# bbshd.net
KiCad netlist of a schematic drawn in EAGLE
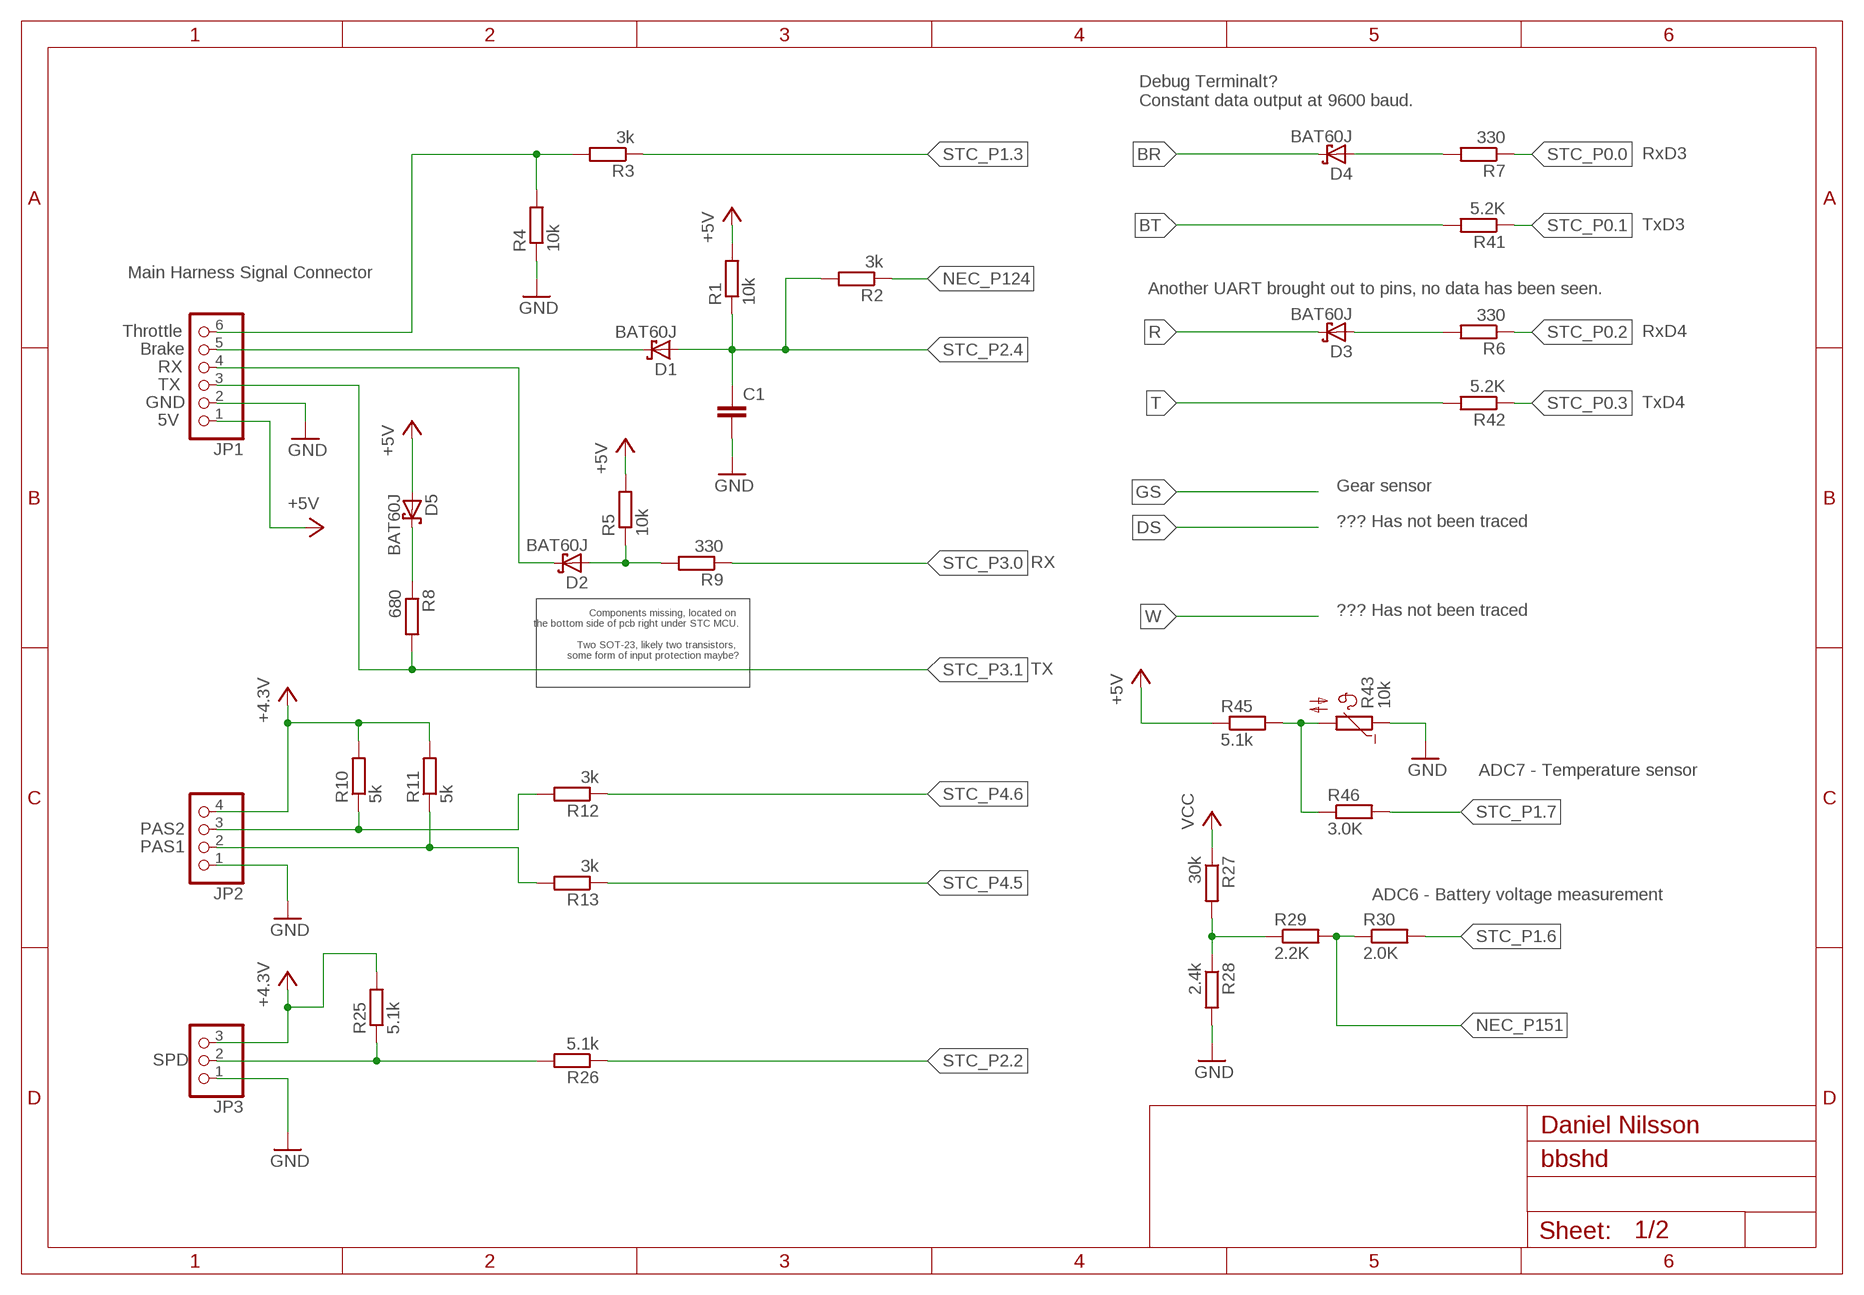
[diagram p0: schematic, sheet 1]
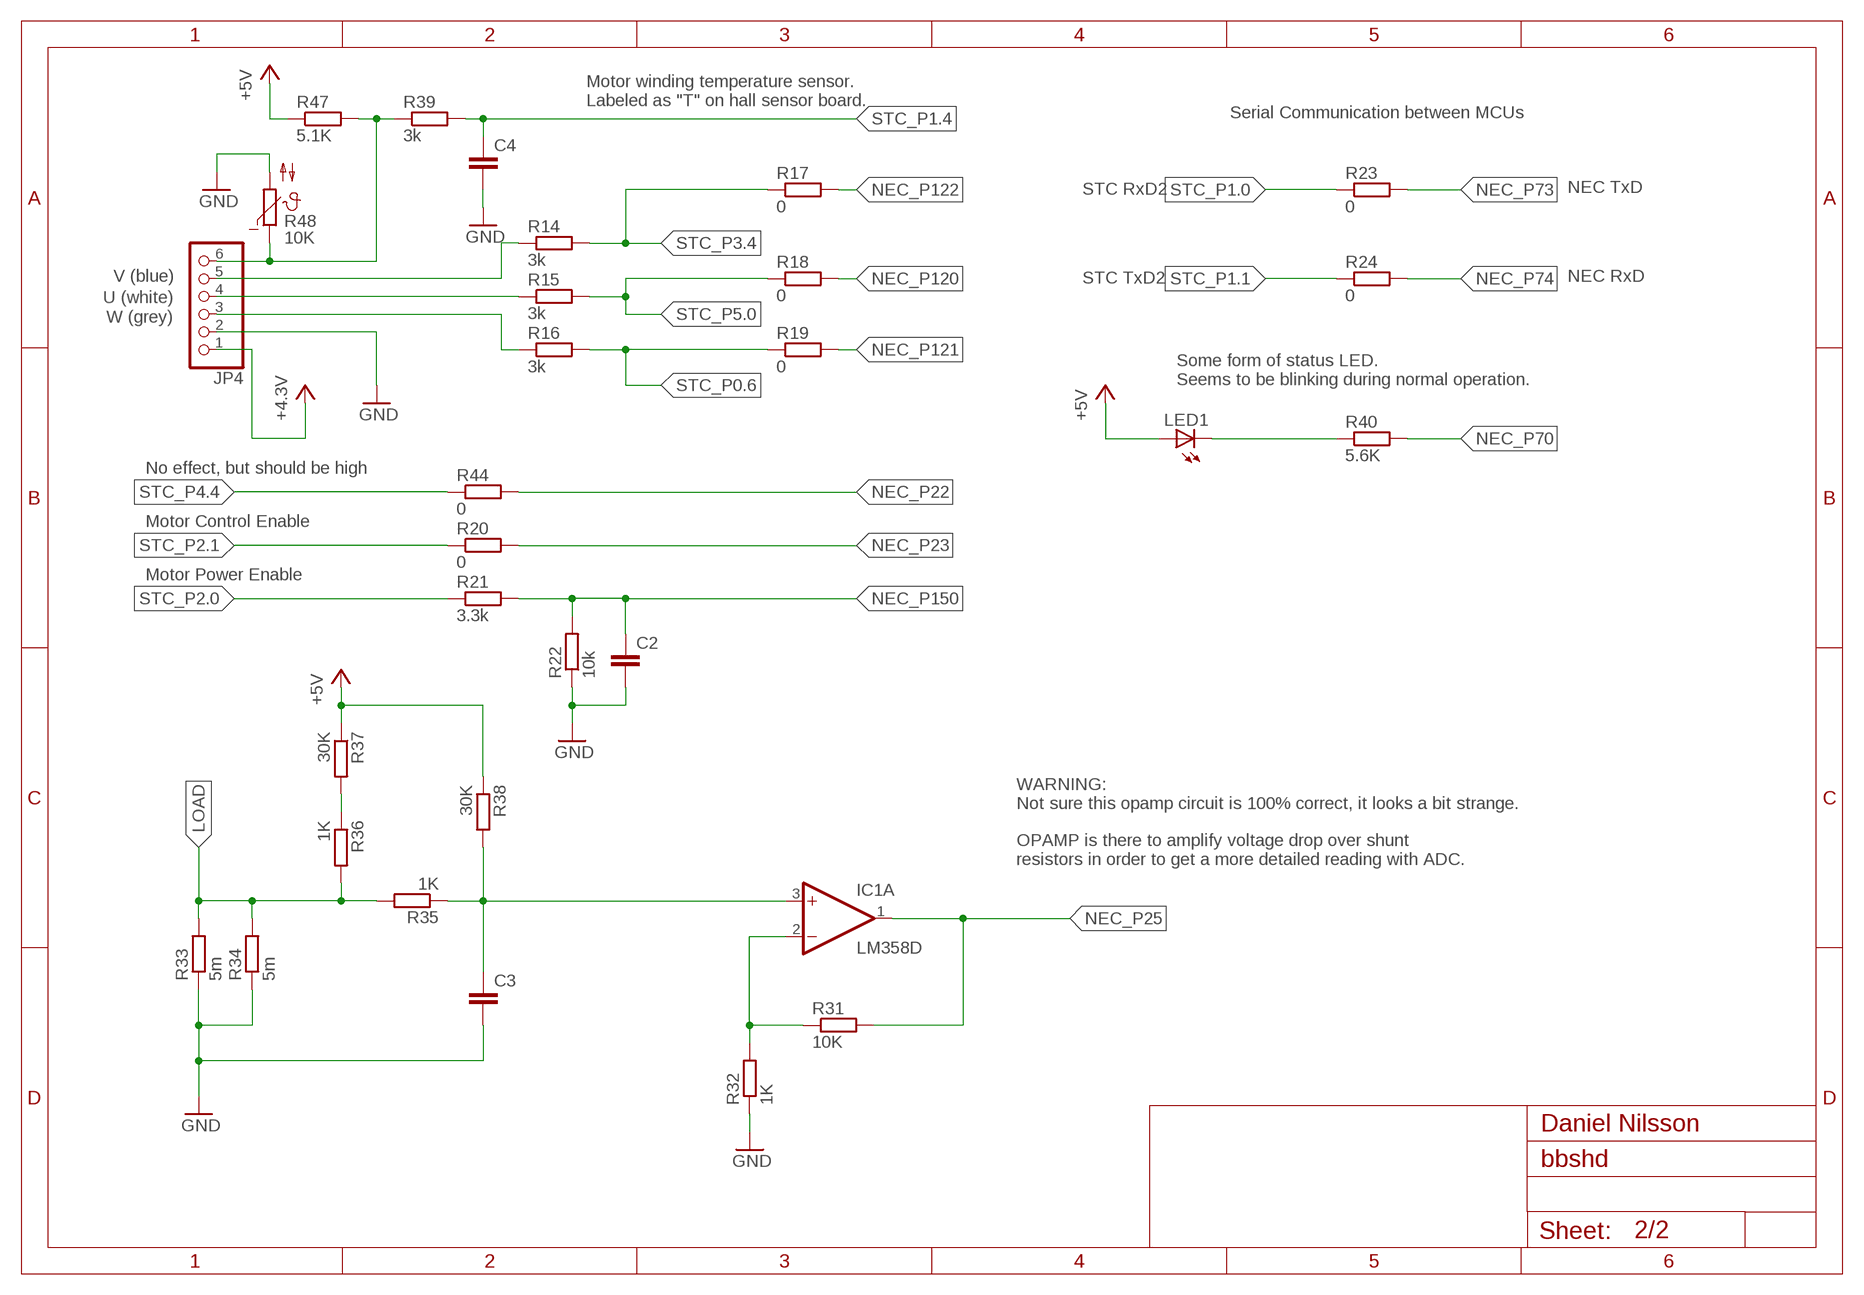
[diagram p1: schematic, sheet 2]

(export (version "E")
  (design (tool "Eeschema 10.0.6"))
  (components
    (comp (ref "C1")
      (value "C-EUC0603")
      (footprint "eagle-import:C0603")
      (libsource (lib "eagle-import") (part "C-EUC0603"))
    )
    (comp (ref "D1")
      (value "BAT60J")
      (footprint "eagle-import:SOD323_ST")
      (libsource (lib "eagle-import") (part "BAT60J"))
    )
    (comp (ref "D2")
      (value "BAT60J")
      (footprint "eagle-import:SOD323_ST")
      (libsource (lib "eagle-import") (part "BAT60J"))
    )
    (comp (ref "D3")
      (value "BAT60J")
      (footprint "eagle-import:SOD323_ST")
      (libsource (lib "eagle-import") (part "BAT60J"))
    )
    (comp (ref "D4")
      (value "BAT60J")
      (footprint "eagle-import:SOD323_ST")
      (libsource (lib "eagle-import") (part "BAT60J"))
    )
    (comp (ref "D5")
      (value "BAT60J")
      (footprint "eagle-import:SOD323_ST")
      (libsource (lib "eagle-import") (part "BAT60J"))
    )
    (comp (ref "JP1")
      (value "PINHD-1X6")
      (footprint "eagle-import:1X06")
      (libsource (lib "eagle-import") (part "PINHD-1X6"))
    )
    (comp (ref "JP2")
      (value "PINHD-1X4")
      (footprint "eagle-import:1X04")
      (libsource (lib "eagle-import") (part "PINHD-1X4"))
    )
    (comp (ref "JP3")
      (value "PINHD-1X3")
      (footprint "eagle-import:1X03")
      (libsource (lib "eagle-import") (part "PINHD-1X3"))
    )
    (comp (ref "R1")
      (value "10k")
      (footprint "eagle-import:R0603")
      (libsource (lib "eagle-import") (part "R-EU_R0603"))
    )
    (comp (ref "R2")
      (value "3k")
      (footprint "eagle-import:R0603")
      (libsource (lib "eagle-import") (part "R-EU_R0603"))
    )
    (comp (ref "R3")
      (value "3k")
      (footprint "eagle-import:R0603")
      (libsource (lib "eagle-import") (part "R-EU_R0603"))
    )
    (comp (ref "R4")
      (value "10k")
      (footprint "eagle-import:R0603")
      (libsource (lib "eagle-import") (part "R-EU_R0603"))
    )
    (comp (ref "R5")
      (value "10k")
      (footprint "eagle-import:R0603")
      (libsource (lib "eagle-import") (part "R-EU_R0603"))
    )
    (comp (ref "R6")
      (value "330")
      (footprint "eagle-import:R0603")
      (libsource (lib "eagle-import") (part "R-EU_R0603"))
    )
    (comp (ref "R7")
      (value "330")
      (footprint "eagle-import:R0603")
      (libsource (lib "eagle-import") (part "R-EU_R0603"))
    )
    (comp (ref "R8")
      (value "680")
      (footprint "eagle-import:R0603")
      (libsource (lib "eagle-import") (part "R-EU_R0603"))
    )
    (comp (ref "R9")
      (value "330")
      (footprint "eagle-import:R0603")
      (libsource (lib "eagle-import") (part "R-EU_R0603"))
    )
    (comp (ref "R10")
      (value "5k")
      (footprint "eagle-import:R0603")
      (libsource (lib "eagle-import") (part "R-EU_R0603"))
    )
    (comp (ref "R11")
      (value "5k")
      (footprint "eagle-import:R0603")
      (libsource (lib "eagle-import") (part "R-EU_R0603"))
    )
    (comp (ref "R12")
      (value "3k")
      (footprint "eagle-import:R0603")
      (libsource (lib "eagle-import") (part "R-EU_R0603"))
    )
    (comp (ref "R13")
      (value "3k")
      (footprint "eagle-import:R0603")
      (libsource (lib "eagle-import") (part "R-EU_R0603"))
    )
    (comp (ref "R25")
      (value "5.1k")
      (footprint "eagle-import:R0603")
      (libsource (lib "eagle-import") (part "R-EU_R0603"))
    )
    (comp (ref "R26")
      (value "5.1k")
      (footprint "eagle-import:R0603")
      (libsource (lib "eagle-import") (part "R-EU_R0603"))
    )
    (comp (ref "R27")
      (value "30k")
      (footprint "eagle-import:R0603")
      (libsource (lib "eagle-import") (part "R-EU_R0603"))
    )
    (comp (ref "R28")
      (value "2.4k")
      (footprint "eagle-import:R0603")
      (libsource (lib "eagle-import") (part "R-EU_R0603"))
    )
    (comp (ref "R29")
      (value "2.2K")
      (footprint "eagle-import:R0603")
      (libsource (lib "eagle-import") (part "R-EU_R0603"))
    )
    (comp (ref "R30")
      (value "2.0K")
      (footprint "eagle-import:R0603")
      (libsource (lib "eagle-import") (part "R-EU_R0603"))
    )
    (comp (ref "R41")
      (value "5.2K")
      (footprint "eagle-import:R0603")
      (libsource (lib "eagle-import") (part "R-EU_R0603"))
    )
    (comp (ref "R42")
      (value "5.2K")
      (footprint "eagle-import:R0603")
      (libsource (lib "eagle-import") (part "R-EU_R0603"))
    )
    (comp (ref "R43")
      (value "10k")
      (footprint "eagle-import:P640")
      (libsource (lib "eagle-import") (part "NTC640"))
    )
    (comp (ref "R45")
      (value "5.1k")
      (footprint "eagle-import:R0603")
      (libsource (lib "eagle-import") (part "R-EU_R0603"))
    )
    (comp (ref "R46")
      (value "3.0K")
      (footprint "eagle-import:R0603")
      (libsource (lib "eagle-import") (part "R-EU_R0603"))
    )
    (comp (ref "C2")
      (value "C-EUC0603")
      (footprint "eagle-import:C0603")
      (libsource (lib "eagle-import") (part "C-EUC0603"))
    )
    (comp (ref "C3")
      (value "C-EUC0603")
      (footprint "eagle-import:C0603")
      (libsource (lib "eagle-import") (part "C-EUC0603"))
    )
    (comp (ref "C4")
      (value "C-EUC0603")
      (footprint "eagle-import:C0603")
      (libsource (lib "eagle-import") (part "C-EUC0603"))
    )
    (comp (ref "IC1")
      (value "LM358D")
      (footprint "eagle-import:SO08")
      (libsource (lib "eagle-import") (part "LM358D"))
    )
    (comp (ref "JP4")
      (value "PINHD-1X6")
      (footprint "eagle-import:1X06")
      (libsource (lib "eagle-import") (part "PINHD-1X6"))
    )
    (comp (ref "LED1")
      (value "LED")
      (footprint "eagle-import:SMARTLED-TTW")
      (libsource (lib "eagle-import") (part "LED"))
    )
    (comp (ref "R14")
      (value "3k")
      (footprint "eagle-import:R0603")
      (libsource (lib "eagle-import") (part "R-EU_R0603"))
    )
    (comp (ref "R15")
      (value "3k")
      (footprint "eagle-import:R0603")
      (libsource (lib "eagle-import") (part "R-EU_R0603"))
    )
    (comp (ref "R16")
      (value "3k")
      (footprint "eagle-import:R0603")
      (libsource (lib "eagle-import") (part "R-EU_R0603"))
    )
    (comp (ref "R17")
      (value "0")
      (footprint "eagle-import:R0603")
      (libsource (lib "eagle-import") (part "R-EU_R0603"))
    )
    (comp (ref "R18")
      (value "0")
      (footprint "eagle-import:R0603")
      (libsource (lib "eagle-import") (part "R-EU_R0603"))
    )
    (comp (ref "R19")
      (value "0")
      (footprint "eagle-import:R0603")
      (libsource (lib "eagle-import") (part "R-EU_R0603"))
    )
    (comp (ref "R20")
      (value "0")
      (footprint "eagle-import:R0603")
      (libsource (lib "eagle-import") (part "R-EU_R0603"))
    )
    (comp (ref "R21")
      (value "3.3k")
      (footprint "eagle-import:R0603")
      (libsource (lib "eagle-import") (part "R-EU_R0603"))
    )
    (comp (ref "R22")
      (value "10k")
      (footprint "eagle-import:R0603")
      (libsource (lib "eagle-import") (part "R-EU_R0603"))
    )
    (comp (ref "R23")
      (value "0")
      (footprint "eagle-import:R0603")
      (libsource (lib "eagle-import") (part "R-EU_R0603"))
    )
    (comp (ref "R24")
      (value "0")
      (footprint "eagle-import:R0603")
      (libsource (lib "eagle-import") (part "R-EU_R0603"))
    )
    (comp (ref "R31")
      (value "10K")
      (footprint "eagle-import:R0603")
      (libsource (lib "eagle-import") (part "R-EU_R0603"))
    )
    (comp (ref "R32")
      (value "1K")
      (footprint "eagle-import:R0603")
      (libsource (lib "eagle-import") (part "R-EU_R0603"))
    )
    (comp (ref "R33")
      (value "5m")
      (footprint "eagle-import:R0603")
      (libsource (lib "eagle-import") (part "R-EU_R0603"))
    )
    (comp (ref "R34")
      (value "5m")
      (footprint "eagle-import:R0603")
      (libsource (lib "eagle-import") (part "R-EU_R0603"))
    )
    (comp (ref "R35")
      (value "1K")
      (footprint "eagle-import:R0603")
      (libsource (lib "eagle-import") (part "R-EU_R0603"))
    )
    (comp (ref "R36")
      (value "1K")
      (footprint "eagle-import:R0603")
      (libsource (lib "eagle-import") (part "R-EU_R0603"))
    )
    (comp (ref "R37")
      (value "30K")
      (footprint "eagle-import:R0603")
      (libsource (lib "eagle-import") (part "R-EU_R0603"))
    )
    (comp (ref "R38")
      (value "30K")
      (footprint "eagle-import:R0603")
      (libsource (lib "eagle-import") (part "R-EU_R0603"))
    )
    (comp (ref "R39")
      (value "3k")
      (footprint "eagle-import:R0603")
      (libsource (lib "eagle-import") (part "R-EU_R0603"))
    )
    (comp (ref "R40")
      (value "5.6K")
      (footprint "eagle-import:R0603")
      (libsource (lib "eagle-import") (part "R-EU_R0603"))
    )
    (comp (ref "R44")
      (value "0")
      (footprint "eagle-import:R0603")
      (libsource (lib "eagle-import") (part "R-EU_R0603"))
    )
    (comp (ref "R47")
      (value "5.1K")
      (footprint "eagle-import:R0603")
      (libsource (lib "eagle-import") (part "R-EU_R0603"))
    )
    (comp (ref "R48")
      (value "10K")
      (footprint "eagle-import:P642")
      (libsource (lib "eagle-import") (part "NTC642-6"))
    )
  )
  (nets
    (net (code "1") (name "+3V3") (class "Default")
      (node (ref "JP2") (pin "4") (pinfunction "4_4") (pintype "passive"))
      (node (ref "JP3") (pin "3") (pinfunction "3_3") (pintype "passive"))
      (node (ref "JP4") (pin "1") (pinfunction "1_1") (pintype "passive"))
      (node (ref "R10") (pin "2") (pinfunction "2_2") (pintype "passive"))
      (node (ref "R11") (pin "2") (pinfunction "2_2") (pintype "passive"))
      (node (ref "R25") (pin "2") (pinfunction "2_2") (pintype "passive"))
    )
    (net (code "2") (name "+5V") (class "Default")
      (node (ref "D5") (pin "A") (pinfunction "A_A") (pintype "passive"))
      (node (ref "JP1") (pin "1") (pinfunction "1_1") (pintype "passive"))
      (node (ref "LED1") (pin "A@1") (pinfunction "A_A@1") (pintype "passive"))
      (node (ref "R1") (pin "2") (pinfunction "2_2") (pintype "passive"))
      (node (ref "R37") (pin "1") (pinfunction "1_1") (pintype "passive"))
      (node (ref "R38") (pin "1") (pinfunction "1_1") (pintype "passive"))
      (node (ref "R45") (pin "1") (pinfunction "1_1") (pintype "passive"))
      (node (ref "R47") (pin "1") (pinfunction "1_1") (pintype "passive"))
      (node (ref "R5") (pin "2") (pinfunction "2_2") (pintype "passive"))
    )
    (net (code "3") (name "BR") (class "Default")
      (node (ref "D4") (pin "C") (pinfunction "C_C") (pintype "passive"))
    )
    (net (code "4") (name "BT") (class "Default")
      (node (ref "R41") (pin "2") (pinfunction "2_2") (pintype "passive"))
    )
    (net (code "6") (name "GND") (class "Default")
      (node (ref "C1") (pin "2") (pinfunction "2_2") (pintype "passive"))
      (node (ref "C2") (pin "2") (pinfunction "2_2") (pintype "passive"))
      (node (ref "C3") (pin "2") (pinfunction "2_2") (pintype "passive"))
      (node (ref "C4") (pin "2") (pinfunction "2_2") (pintype "passive"))
      (node (ref "JP1") (pin "2") (pinfunction "2_2") (pintype "passive"))
      (node (ref "JP2") (pin "1") (pinfunction "1_1") (pintype "passive"))
      (node (ref "JP3") (pin "1") (pinfunction "1_1") (pintype "passive"))
      (node (ref "JP4") (pin "2") (pinfunction "2_2") (pintype "passive"))
      (node (ref "R22") (pin "1") (pinfunction "1_1") (pintype "passive"))
      (node (ref "R28") (pin "2") (pinfunction "2_2") (pintype "passive"))
      (node (ref "R32") (pin "1") (pinfunction "1_1") (pintype "passive"))
      (node (ref "R33") (pin "1") (pinfunction "1_1") (pintype "passive"))
      (node (ref "R34") (pin "1") (pinfunction "1_1") (pintype "passive"))
      (node (ref "R4") (pin "1") (pinfunction "1_1") (pintype "passive"))
      (node (ref "R43") (pin "1") (pinfunction "1_1") (pintype "passive"))
      (node (ref "R48") (pin "2") (pinfunction "2_2") (pintype "passive"))
    )
    (net (code "8") (name "LOAD") (class "Default")
      (node (ref "R33") (pin "2") (pinfunction "2_2") (pintype "passive"))
      (node (ref "R34") (pin "2") (pinfunction "2_2") (pintype "passive"))
      (node (ref "R35") (pin "2") (pinfunction "2_2") (pintype "passive"))
      (node (ref "R36") (pin "2") (pinfunction "2_2") (pintype "passive"))
    )
    (net (code "9") (name "NEC_P22") (class "Default")
      (node (ref "R44") (pin "2") (pinfunction "2_2") (pintype "passive"))
    )
    (net (code "10") (name "NEC_P23") (class "Default")
      (node (ref "R20") (pin "2") (pinfunction "2_2") (pintype "passive"))
    )
    (net (code "11") (name "NEC_P25") (class "Default")
      (node (ref "IC1") (pin "1") (pinfunction "OUT_1") (pintype "output"))
      (node (ref "R31") (pin "2") (pinfunction "2_2") (pintype "passive"))
    )
    (net (code "12") (name "NEC_P70") (class "Default")
      (node (ref "R40") (pin "2") (pinfunction "2_2") (pintype "passive"))
    )
    (net (code "13") (name "NEC_P73") (class "Default")
      (node (ref "R23") (pin "2") (pinfunction "2_2") (pintype "passive"))
    )
    (net (code "14") (name "NEC_P74") (class "Default")
      (node (ref "R24") (pin "2") (pinfunction "2_2") (pintype "passive"))
    )
    (net (code "15") (name "NEC_P120") (class "Default")
      (node (ref "R18") (pin "2") (pinfunction "2_2") (pintype "passive"))
    )
    (net (code "16") (name "NEC_P121") (class "Default")
      (node (ref "R19") (pin "2") (pinfunction "2_2") (pintype "passive"))
    )
    (net (code "17") (name "NEC_P122") (class "Default")
      (node (ref "R17") (pin "2") (pinfunction "2_2") (pintype "passive"))
    )
    (net (code "18") (name "NEC_P124") (class "Default")
      (node (ref "R2") (pin "1") (pinfunction "1_1") (pintype "passive"))
    )
    (net (code "19") (name "NEC_P150") (class "Default")
      (node (ref "C2") (pin "1") (pinfunction "1_1") (pintype "passive"))
      (node (ref "R21") (pin "2") (pinfunction "2_2") (pintype "passive"))
      (node (ref "R22") (pin "2") (pinfunction "2_2") (pintype "passive"))
    )
    (net (code "20") (name "NEC_P151") (class "Default")
      (node (ref "R29") (pin "2") (pinfunction "2_2") (pintype "passive"))
      (node (ref "R30") (pin "1") (pinfunction "1_1") (pintype "passive"))
    )
    (net (code "21") (name "Net-(D1-PadC)") (class "Default")
      (node (ref "D1") (pin "C") (pinfunction "C_C") (pintype "passive"))
      (node (ref "JP1") (pin "5") (pinfunction "5_5") (pintype "passive"))
    )
    (net (code "22") (name "Net-(D2-PadA)") (class "Default")
      (node (ref "D2") (pin "A") (pinfunction "A_A") (pintype "passive"))
      (node (ref "R5") (pin "1") (pinfunction "1_1") (pintype "passive"))
      (node (ref "R9") (pin "2") (pinfunction "2_2") (pintype "passive"))
    )
    (net (code "23") (name "Net-(D2-PadC)") (class "Default")
      (node (ref "D2") (pin "C") (pinfunction "C_C") (pintype "passive"))
      (node (ref "JP1") (pin "4") (pinfunction "4_4") (pintype "passive"))
    )
    (net (code "24") (name "Net-(D3-PadA)") (class "Default")
      (node (ref "D3") (pin "A") (pinfunction "A_A") (pintype "passive"))
      (node (ref "R6") (pin "2") (pinfunction "2_2") (pintype "passive"))
    )
    (net (code "25") (name "Net-(D4-PadA)") (class "Default")
      (node (ref "D4") (pin "A") (pinfunction "A_A") (pintype "passive"))
      (node (ref "R7") (pin "2") (pinfunction "2_2") (pintype "passive"))
    )
    (net (code "26") (name "Net-(D5-PadC)") (class "Default")
      (node (ref "D5") (pin "C") (pinfunction "C_C") (pintype "passive"))
      (node (ref "R8") (pin "1") (pinfunction "1_1") (pintype "passive"))
    )
    (net (code "27") (name "Net-(IC1A-+IN)") (class "Default")
      (node (ref "C3") (pin "1") (pinfunction "1_1") (pintype "passive"))
      (node (ref "IC1") (pin "3") (pinfunction "+IN_3") (pintype "input"))
      (node (ref "R35") (pin "1") (pinfunction "1_1") (pintype "passive"))
      (node (ref "R38") (pin "2") (pinfunction "2_2") (pintype "passive"))
    )
    (net (code "28") (name "Net-(IC1A--IN)") (class "Default")
      (node (ref "IC1") (pin "2") (pinfunction "-IN_2") (pintype "input"))
      (node (ref "R31") (pin "1") (pinfunction "1_1") (pintype "passive"))
      (node (ref "R32") (pin "2") (pinfunction "2_2") (pintype "passive"))
    )
    (net (code "29") (name "Net-(JP1-Pad6)") (class "Default")
      (node (ref "JP1") (pin "6") (pinfunction "6_6") (pintype "passive"))
      (node (ref "R3") (pin "2") (pinfunction "2_2") (pintype "passive"))
      (node (ref "R4") (pin "2") (pinfunction "2_2") (pintype "passive"))
    )
    (net (code "30") (name "Net-(JP2-Pad2)") (class "Default")
      (node (ref "JP2") (pin "2") (pinfunction "2_2") (pintype "passive"))
      (node (ref "R11") (pin "1") (pinfunction "1_1") (pintype "passive"))
      (node (ref "R13") (pin "2") (pinfunction "2_2") (pintype "passive"))
    )
    (net (code "31") (name "Net-(JP2-Pad3)") (class "Default")
      (node (ref "JP2") (pin "3") (pinfunction "3_3") (pintype "passive"))
      (node (ref "R10") (pin "1") (pinfunction "1_1") (pintype "passive"))
      (node (ref "R12") (pin "2") (pinfunction "2_2") (pintype "passive"))
    )
    (net (code "32") (name "Net-(JP3-Pad2)") (class "Default")
      (node (ref "JP3") (pin "2") (pinfunction "2_2") (pintype "passive"))
      (node (ref "R25") (pin "1") (pinfunction "1_1") (pintype "passive"))
      (node (ref "R26") (pin "2") (pinfunction "2_2") (pintype "passive"))
    )
    (net (code "33") (name "Net-(JP4-Pad3)") (class "Default")
      (node (ref "JP4") (pin "3") (pinfunction "3_3") (pintype "passive"))
      (node (ref "R16") (pin "1") (pinfunction "1_1") (pintype "passive"))
    )
    (net (code "34") (name "Net-(JP4-Pad4)") (class "Default")
      (node (ref "JP4") (pin "4") (pinfunction "4_4") (pintype "passive"))
      (node (ref "R15") (pin "1") (pinfunction "1_1") (pintype "passive"))
    )
    (net (code "35") (name "Net-(JP4-Pad5)") (class "Default")
      (node (ref "JP4") (pin "5") (pinfunction "5_5") (pintype "passive"))
      (node (ref "R14") (pin "1") (pinfunction "1_1") (pintype "passive"))
    )
    (net (code "36") (name "Net-(JP4-Pad6)") (class "Default")
      (node (ref "JP4") (pin "6") (pinfunction "6_6") (pintype "passive"))
      (node (ref "R39") (pin "1") (pinfunction "1_1") (pintype "passive"))
      (node (ref "R47") (pin "2") (pinfunction "2_2") (pintype "passive"))
      (node (ref "R48") (pin "1") (pinfunction "1_1") (pintype "passive"))
    )
    (net (code "37") (name "Net-(LED1-C)") (class "Default")
      (node (ref "LED1") (pin "C@1") (pinfunction "C_C@1") (pintype "passive"))
      (node (ref "R40") (pin "1") (pinfunction "1_1") (pintype "passive"))
    )
    (net (code "38") (name "Net-(R27-Pad2)") (class "Default")
      (node (ref "R27") (pin "2") (pinfunction "2_2") (pintype "passive"))
      (node (ref "R28") (pin "1") (pinfunction "1_1") (pintype "passive"))
      (node (ref "R29") (pin "1") (pinfunction "1_1") (pintype "passive"))
    )
    (net (code "39") (name "Net-(R36-Pad1)") (class "Default")
      (node (ref "R36") (pin "1") (pinfunction "1_1") (pintype "passive"))
      (node (ref "R37") (pin "2") (pinfunction "2_2") (pintype "passive"))
    )
    (net (code "40") (name "Net-(R43-Pad2)") (class "Default")
      (node (ref "R43") (pin "2") (pinfunction "2_2") (pintype "passive"))
      (node (ref "R45") (pin "2") (pinfunction "2_2") (pintype "passive"))
      (node (ref "R46") (pin "1") (pinfunction "1_1") (pintype "passive"))
    )
    (net (code "41") (name "R") (class "Default")
      (node (ref "D3") (pin "C") (pinfunction "C_C") (pintype "passive"))
    )
    (net (code "42") (name "STC_P0.0") (class "Default")
      (node (ref "R7") (pin "1") (pinfunction "1_1") (pintype "passive"))
    )
    (net (code "43") (name "STC_P0.1") (class "Default")
      (node (ref "R41") (pin "1") (pinfunction "1_1") (pintype "passive"))
    )
    (net (code "44") (name "STC_P0.2") (class "Default")
      (node (ref "R6") (pin "1") (pinfunction "1_1") (pintype "passive"))
    )
    (net (code "45") (name "STC_P0.3") (class "Default")
      (node (ref "R42") (pin "1") (pinfunction "1_1") (pintype "passive"))
    )
    (net (code "46") (name "STC_P0.6") (class "Default")
      (node (ref "R16") (pin "2") (pinfunction "2_2") (pintype "passive"))
      (node (ref "R19") (pin "1") (pinfunction "1_1") (pintype "passive"))
    )
    (net (code "47") (name "STC_P1.0") (class "Default")
      (node (ref "R23") (pin "1") (pinfunction "1_1") (pintype "passive"))
    )
    (net (code "48") (name "STC_P1.1") (class "Default")
      (node (ref "R24") (pin "1") (pinfunction "1_1") (pintype "passive"))
    )
    (net (code "49") (name "STC_P1.3") (class "Default")
      (node (ref "R3") (pin "1") (pinfunction "1_1") (pintype "passive"))
    )
    (net (code "50") (name "STC_P1.4") (class "Default")
      (node (ref "C4") (pin "1") (pinfunction "1_1") (pintype "passive"))
      (node (ref "R39") (pin "2") (pinfunction "2_2") (pintype "passive"))
    )
    (net (code "51") (name "STC_P1.6") (class "Default")
      (node (ref "R30") (pin "2") (pinfunction "2_2") (pintype "passive"))
    )
    (net (code "52") (name "STC_P1.7") (class "Default")
      (node (ref "R46") (pin "2") (pinfunction "2_2") (pintype "passive"))
    )
    (net (code "53") (name "STC_P2.0") (class "Default")
      (node (ref "R21") (pin "1") (pinfunction "1_1") (pintype "passive"))
    )
    (net (code "54") (name "STC_P2.1") (class "Default")
      (node (ref "R20") (pin "1") (pinfunction "1_1") (pintype "passive"))
    )
    (net (code "55") (name "STC_P2.2") (class "Default")
      (node (ref "R26") (pin "1") (pinfunction "1_1") (pintype "passive"))
    )
    (net (code "56") (name "STC_P2.4") (class "Default")
      (node (ref "C1") (pin "1") (pinfunction "1_1") (pintype "passive"))
      (node (ref "D1") (pin "A") (pinfunction "A_A") (pintype "passive"))
      (node (ref "R1") (pin "1") (pinfunction "1_1") (pintype "passive"))
      (node (ref "R2") (pin "2") (pinfunction "2_2") (pintype "passive"))
    )
    (net (code "57") (name "STC_P3.0") (class "Default")
      (node (ref "R9") (pin "1") (pinfunction "1_1") (pintype "passive"))
    )
    (net (code "58") (name "STC_P3.1") (class "Default")
      (node (ref "JP1") (pin "3") (pinfunction "3_3") (pintype "passive"))
      (node (ref "R8") (pin "2") (pinfunction "2_2") (pintype "passive"))
    )
    (net (code "59") (name "STC_P3.4") (class "Default")
      (node (ref "R14") (pin "2") (pinfunction "2_2") (pintype "passive"))
      (node (ref "R17") (pin "1") (pinfunction "1_1") (pintype "passive"))
    )
    (net (code "60") (name "STC_P4.4") (class "Default")
      (node (ref "R44") (pin "1") (pinfunction "1_1") (pintype "passive"))
    )
    (net (code "61") (name "STC_P4.5") (class "Default")
      (node (ref "R13") (pin "1") (pinfunction "1_1") (pintype "passive"))
    )
    (net (code "62") (name "STC_P4.6") (class "Default")
      (node (ref "R12") (pin "1") (pinfunction "1_1") (pintype "passive"))
    )
    (net (code "63") (name "STC_P5.0") (class "Default")
      (node (ref "R15") (pin "2") (pinfunction "2_2") (pintype "passive"))
      (node (ref "R18") (pin "1") (pinfunction "1_1") (pintype "passive"))
    )
    (net (code "64") (name "T") (class "Default")
      (node (ref "R42") (pin "2") (pinfunction "2_2") (pintype "passive"))
    )
    (net (code "65") (name "VCC") (class "Default")
      (node (ref "R27") (pin "1") (pinfunction "1_1") (pintype "passive"))
    )
  )
)
